# I2C.net
KiCad netlist of a schematic drawn in Altium Designer
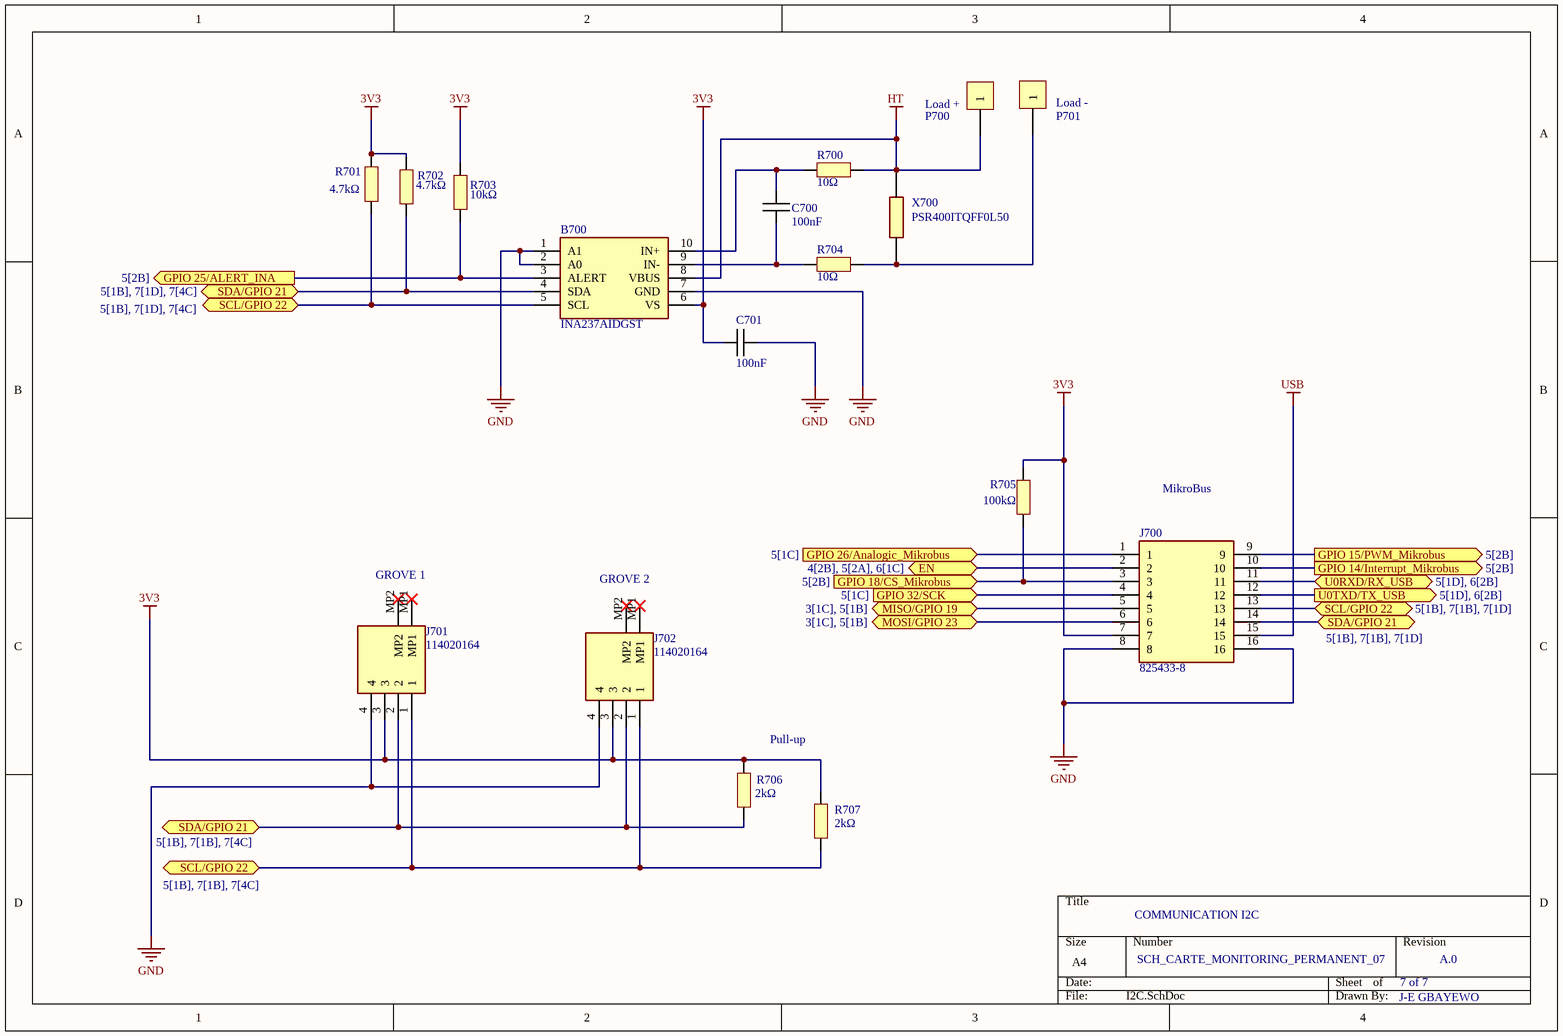
[diagram p0: I2C.SchDoc]

(export (version "E")
  (design (tool "Eeschema 10.0.6"))
  (components
    (comp (ref "B700")
      (value "INA237AIDGST")
      (footprint "SOP50P490X110-10N")
      (fields (field (name "MOUSER PART NUMBER") "595-INA237AIDGST"))
      (libsource (lib "SCHLibrary") (part "INA237AIDGST"))
    )
    (comp (ref "C700")
      (value "100nF")
      (footprint "CAPC1005X06N")
      (libsource (lib "SCHLibrary") (part "Capacitor"))
    )
    (comp (ref "C701")
      (value "100nF")
      (footprint "CAPC1005X06N")
      (libsource (lib "SCHLibrary") (part "Capacitor"))
    )
    (comp (ref "J700")
      (value "825433-8")
      (footprint "Connect-Mikrobus")
      (description "Headers & Wire Housings 8P double for connection mikrobus")
      (fields (field (name "MOUSER PART NUMBER") "571-825433-8"))
      (libsource (lib "SCHLibrary") (part "Connect-Mikrobus"))
    )
    (comp (ref "J701")
      (value "114020164")
      (footprint "114020164")
      (description "Seeed Studio Accessories Grove Female Header - SMD-4P-2.0mm-90D-20Pcs")
      (fields (field (name "MOUSER PART NUMBER") "713-114020164"))
      (libsource (lib "SCHLibrary") (part "114020164"))
    )
    (comp (ref "J702")
      (value "114020164")
      (footprint "114020164")
      (description "Seeed Studio Accessories Grove Female Header - SMD-4P-2.0mm-90D-20Pcs")
      (fields (field (name "MOUSER PART NUMBER") "713-114020164"))
      (libsource (lib "SCHLibrary") (part "114020164"))
    )
    (comp (ref "P700")
      (value "Plage CMS 10x5")
      (footprint "Plage CMS 10x5")
      (description "Plage de report CMS 10x5mm")
      (libsource (lib "SCHLibrary") (part "Plage CMS 10x5"))
    )
    (comp (ref "P701")
      (value "Plage CMS 10x5")
      (footprint "Plage CMS 10x5")
      (description "Plage de report CMS 10x5mm")
      (libsource (lib "SCHLibrary") (part "Plage CMS 10x5"))
    )
    (comp (ref "R700") (value "10Ω") (footprint "RESC1005X06N") (libsource (lib "") (part "Resistor_1")))
    (comp (ref "R701")
      (value "4.7kΩ")
      (footprint "RESC1005X06N")
      (libsource (lib "SCHLibrary") (part "Resistor"))
    )
    (comp (ref "R702")
      (value "4.7kΩ")
      (footprint "RESC1005X06N")
      (libsource (lib "SCHLibrary") (part "Resistor"))
    )
    (comp (ref "R703") (value "10kΩ") (footprint "RESC1005X06N") (libsource (lib "") (part "Resistor_2")))
    (comp (ref "R704") (value "10Ω") (footprint "RESC1005X06N") (libsource (lib "") (part "Resistor_1")))
    (comp (ref "R705") (value "100kΩ") (footprint "RESC1005X06N") (libsource (lib "") (part "Resistor_2")))
    (comp (ref "R706")
      (value "2kΩ")
      (footprint "RESC1005X06N")
      (libsource (lib "SCHLibrary") (part "Resistor"))
    )
    (comp (ref "R707")
      (value "2kΩ")
      (footprint "RESC1005X06N")
      (libsource (lib "SCHLibrary") (part "Resistor"))
    )
    (comp (ref "X700")
      (value "PSR400ITQFF0L50")
      (footprint "RESC10052X200N")
      (fields (field (name "MOUSER PART NUMBER") "755-PSR400ITQFF0L50"))
      (libsource (lib "SCHLibrary") (part "PSR400ITQFF0L50"))
    )
  )
  (nets
    (net (code "2") (name "/EN") (class "Default")
      (node (ref "J700") (pin "2") (pinfunction "2_2") (pintype "passive"))
    )
    (net (code "3") (name "/GPIO 14{slash}Interrupt_Mikrobus") (class "Default")
      (node (ref "J700") (pin "10") (pinfunction "10_10") (pintype "passive"))
    )
    (net (code "4") (name "/GPIO 15{slash}PWM_Mikrobus") (class "Default")
      (node (ref "J700") (pin "9") (pinfunction "9_9") (pintype "passive"))
    )
    (net (code "5") (name "/GPIO 18{slash}CS_Mikrobus") (class "Default")
      (node (ref "J700") (pin "3") (pinfunction "3_3") (pintype "passive"))
      (node (ref "R705") (pin "1") (pinfunction "1_1") (pintype "passive"))
    )
    (net (code "6") (name "/GPIO 25{slash}ALERT_INA") (class "Default")
      (node (ref "B700") (pin "3") (pinfunction "ALERT_3") (pintype "passive"))
      (node (ref "R703") (pin "1") (pinfunction "1_1") (pintype "passive"))
    )
    (net (code "7") (name "/GPIO 26{slash}Analogic_Mikrobus") (class "Default")
      (node (ref "J700") (pin "1") (pinfunction "1_1") (pintype "passive"))
    )
    (net (code "8") (name "/GPIO 32{slash}SCK") (class "Default")
      (node (ref "J700") (pin "4") (pinfunction "4_4") (pintype "passive"))
    )
    (net (code "9") (name "/MISO{slash}GPIO 19") (class "Default")
      (node (ref "J700") (pin "5") (pinfunction "5_5") (pintype "passive"))
    )
    (net (code "10") (name "/MOSI{slash}GPIO 23") (class "Default")
      (node (ref "J700") (pin "6") (pinfunction "6_6") (pintype "passive"))
    )
    (net (code "11") (name "/SCL{slash}GPIO 22") (class "Default")
      (node (ref "B700") (pin "5") (pinfunction "SCL_5") (pintype "passive"))
      (node (ref "J700") (pin "13") (pinfunction "13_13") (pintype "passive"))
      (node (ref "J701") (pin "1") (pinfunction "1_1") (pintype "passive"))
      (node (ref "J702") (pin "1") (pinfunction "1_1") (pintype "passive"))
      (node (ref "R701") (pin "2") (pinfunction "2_2") (pintype "passive"))
      (node (ref "R707") (pin "2") (pinfunction "2_2") (pintype "passive"))
    )
    (net (code "12") (name "/SDA{slash}GPIO 21") (class "Default")
      (node (ref "B700") (pin "4") (pinfunction "SDA_4") (pintype "passive"))
      (node (ref "J700") (pin "14") (pinfunction "14_14") (pintype "passive"))
      (node (ref "J701") (pin "2") (pinfunction "2_2") (pintype "passive"))
      (node (ref "J702") (pin "2") (pinfunction "2_2") (pintype "passive"))
      (node (ref "R702") (pin "2") (pinfunction "2_2") (pintype "passive"))
      (node (ref "R706") (pin "2") (pinfunction "2_2") (pintype "passive"))
    )
    (net (code "13") (name "/U0RXD{slash}RX_USB") (class "Default")
      (node (ref "J700") (pin "11") (pinfunction "11_11") (pintype "passive"))
    )
    (net (code "14") (name "/U0TXD{slash}TX_USB") (class "Default")
      (node (ref "J700") (pin "12") (pinfunction "12_12") (pintype "passive"))
    )
    (net (code "15") (name "3V3") (class "Default")
      (node (ref "B700") (pin "6") (pinfunction "VS_6") (pintype "passive"))
      (node (ref "C701") (pin "1") (pinfunction "1_1") (pintype "passive"))
      (node (ref "J700") (pin "7") (pinfunction "7_7") (pintype "passive"))
      (node (ref "J701") (pin "3") (pinfunction "3_3") (pintype "passive"))
      (node (ref "J702") (pin "3") (pinfunction "3_3") (pintype "passive"))
      (node (ref "R701") (pin "1") (pinfunction "1_1") (pintype "passive"))
      (node (ref "R702") (pin "1") (pinfunction "1_1") (pintype "passive"))
      (node (ref "R703") (pin "2") (pinfunction "2_2") (pintype "passive"))
      (node (ref "R705") (pin "2") (pinfunction "2_2") (pintype "passive"))
      (node (ref "R706") (pin "1") (pinfunction "1_1") (pintype "passive"))
      (node (ref "R707") (pin "1") (pinfunction "1_1") (pintype "passive"))
    )
    (net (code "16") (name "GND") (class "Default")
      (node (ref "B700") (pin "1") (pinfunction "A1_1") (pintype "passive"))
      (node (ref "B700") (pin "2") (pinfunction "A0_2") (pintype "passive"))
      (node (ref "B700") (pin "7") (pinfunction "GND_7") (pintype "passive"))
      (node (ref "C701") (pin "2") (pinfunction "2_2") (pintype "passive"))
      (node (ref "J700") (pin "16") (pinfunction "16_16") (pintype "passive"))
      (node (ref "J700") (pin "8") (pinfunction "8_8") (pintype "passive"))
      (node (ref "J701") (pin "4") (pinfunction "4_4") (pintype "passive"))
      (node (ref "J702") (pin "4") (pinfunction "4_4") (pintype "passive"))
    )
    (net (code "17") (name "HT") (class "Default")
      (node (ref "B700") (pin "8") (pinfunction "VBUS_8") (pintype "passive"))
      (node (ref "P700") (pin "1") (pinfunction "1_1") (pintype "passive"))
      (node (ref "R700") (pin "2") (pinfunction "2_2") (pintype "passive"))
      (node (ref "X700") (pin "2") (pinfunction "2_2") (pintype "passive"))
    )
    (net (code "18") (name "Net-(B700-IN+)") (class "Default")
      (node (ref "B700") (pin "10") (pinfunction "IN+_10") (pintype "passive"))
      (node (ref "C700") (pin "1") (pinfunction "1_1") (pintype "passive"))
      (node (ref "R700") (pin "1") (pinfunction "1_1") (pintype "passive"))
    )
    (net (code "19") (name "Net-(B700-IN-)") (class "Default")
      (node (ref "B700") (pin "9") (pinfunction "IN-_9") (pintype "passive"))
      (node (ref "C700") (pin "2") (pinfunction "2_2") (pintype "passive"))
      (node (ref "R704") (pin "1") (pinfunction "1_1") (pintype "passive"))
    )
    (net (code "20") (name "Net-(P701-Pad1)") (class "Default")
      (node (ref "P701") (pin "1") (pinfunction "1_1") (pintype "passive"))
      (node (ref "R704") (pin "2") (pinfunction "2_2") (pintype "passive"))
      (node (ref "X700") (pin "1") (pinfunction "1_1") (pintype "passive"))
    )
    (net (code "21") (name "USB") (class "Default")
      (node (ref "J700") (pin "15") (pinfunction "15_15") (pintype "passive"))
    )
    (net (code "22") (name "unconnected-(J701-PadMP1)") (class "Default")
      (node (ref "J701") (pin "MP1") (pinfunction "MP1_MP1") (pintype "passive+no_connect"))
    )
    (net (code "23") (name "unconnected-(J701-PadMP2)") (class "Default")
      (node (ref "J701") (pin "MP2") (pinfunction "MP2_MP2") (pintype "passive+no_connect"))
    )
    (net (code "24") (name "unconnected-(J702-PadMP1)") (class "Default")
      (node (ref "J702") (pin "MP1") (pinfunction "MP1_MP1") (pintype "passive+no_connect"))
    )
    (net (code "25") (name "unconnected-(J702-PadMP2)") (class "Default")
      (node (ref "J702") (pin "MP2") (pinfunction "MP2_MP2") (pintype "passive+no_connect"))
    )
  )
)
